# 15V_Regulated_Dual_Power_Supply_Circuit.net
KiCad netlist of a schematic drawn in EAGLE
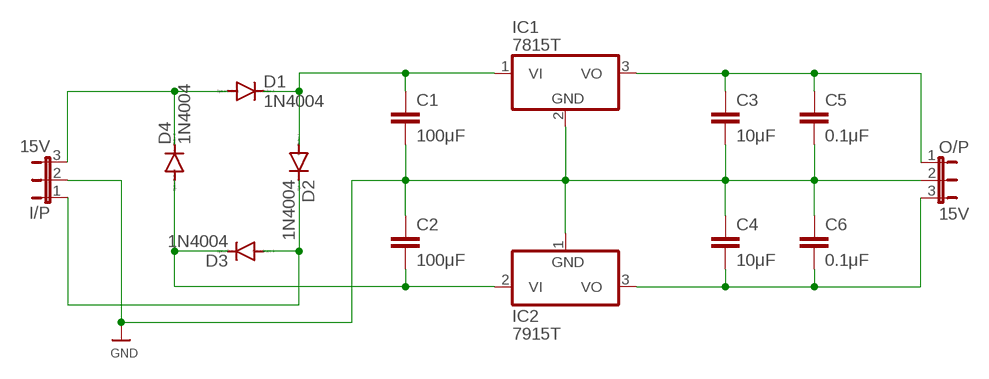
[diagram p0: schematic, sheet 1]

(export (version "E")
  (design (tool "Eeschema 10.0.6"))
  (components
    (comp (ref "C1")
      (value "100μF")
      (footprint "eagle-import:C2.5-2")
      (libsource (lib "eagle-import") (part "C2.5/2"))
    )
    (comp (ref "C2")
      (value "100μF")
      (footprint "eagle-import:C2.5-2")
      (libsource (lib "eagle-import") (part "C2.5/2"))
    )
    (comp (ref "C3")
      (value "10μF")
      (footprint "eagle-import:C2.5-2")
      (libsource (lib "eagle-import") (part "C2.5/2"))
    )
    (comp (ref "C4")
      (value "10μF")
      (footprint "eagle-import:C2.5-2")
      (libsource (lib "eagle-import") (part "C2.5/2"))
    )
    (comp (ref "C5")
      (value "0.1μF")
      (footprint "eagle-import:C2.5-2")
      (libsource (lib "eagle-import") (part "C2.5/2"))
    )
    (comp (ref "C6")
      (value "0.1μF")
      (footprint "eagle-import:C2.5-2")
      (libsource (lib "eagle-import") (part "C2.5/2"))
    )
    (comp (ref "D1")
      (value "1N4004")
      (footprint "eagle-import:DO41-10")
      (libsource (lib "eagle-import") (part "1N4004"))
    )
    (comp (ref "D2")
      (value "1N4004")
      (footprint "eagle-import:DO41-10")
      (libsource (lib "eagle-import") (part "1N4004"))
    )
    (comp (ref "D3")
      (value "1N4004")
      (footprint "eagle-import:DO41-10")
      (libsource (lib "eagle-import") (part "1N4004"))
    )
    (comp (ref "D4")
      (value "1N4004")
      (footprint "eagle-import:DO41-10")
      (libsource (lib "eagle-import") (part "1N4004"))
    )
    (comp (ref "I/P")
      (value "15V")
      (footprint "eagle-import:JP2")
      (libsource (lib "eagle-import") (part "JP2E"))
    )
    (comp (ref "IC1")
      (value "7815T")
      (footprint "eagle-import:TO220H")
      (libsource (lib "eagle-import") (part "78T15"))
    )
    (comp (ref "IC2")
      (value "7915T")
      (footprint "eagle-import:TO220H")
      (libsource (lib "eagle-import") (part "79T15"))
    )
    (comp (ref "O/P")
      (value "15V")
      (footprint "eagle-import:JP2")
      (libsource (lib "eagle-import") (part "JP2E"))
    )
  )
  (nets
    (net (code "1") (name "GND") (class "Default")
      (node (ref "C1") (pin "2") (pinfunction "2_2") (pintype "passive"))
      (node (ref "C2") (pin "1") (pinfunction "1_1") (pintype "passive"))
      (node (ref "C3") (pin "2") (pinfunction "2_2") (pintype "passive"))
      (node (ref "C4") (pin "1") (pinfunction "1_1") (pintype "passive"))
      (node (ref "C5") (pin "2") (pinfunction "2_2") (pintype "passive"))
      (node (ref "C6") (pin "1") (pinfunction "1_1") (pintype "passive"))
      (node (ref "I/P") (pin "2") (pinfunction "2_2") (pintype "passive"))
      (node (ref "IC1") (pin "2") (pinfunction "GND_2") (pintype "passive"))
      (node (ref "IC2") (pin "1") (pinfunction "GND_1") (pintype "passive"))
      (node (ref "O/P") (pin "2") (pinfunction "2_2") (pintype "passive"))
    )
    (net (code "2") (name "Net-(D1-PadA)") (class "Default")
      (node (ref "D1") (pin "A") (pinfunction "A_A") (pintype "passive"))
      (node (ref "D4") (pin "C") (pinfunction "C_C") (pintype "passive"))
      (node (ref "I/P") (pin "3") (pinfunction "3_3") (pintype "passive"))
    )
    (net (code "3") (name "Net-(D2-PadC)") (class "Default")
      (node (ref "D2") (pin "C") (pinfunction "C_C") (pintype "passive"))
      (node (ref "D3") (pin "A") (pinfunction "A_A") (pintype "passive"))
      (node (ref "I/P") (pin "1") (pinfunction "1_1") (pintype "passive"))
    )
    (net (code "4") (name "Net-(IC1-VI)") (class "Default")
      (node (ref "C1") (pin "1") (pinfunction "1_1") (pintype "passive"))
      (node (ref "D1") (pin "C") (pinfunction "C_C") (pintype "passive"))
      (node (ref "D2") (pin "A") (pinfunction "A_A") (pintype "passive"))
      (node (ref "IC1") (pin "1") (pinfunction "VI_1") (pintype "input"))
    )
    (net (code "5") (name "Net-(IC1-VO)") (class "Default")
      (node (ref "C3") (pin "1") (pinfunction "1_1") (pintype "passive"))
      (node (ref "C5") (pin "1") (pinfunction "1_1") (pintype "passive"))
      (node (ref "IC1") (pin "3") (pinfunction "VO_3") (pintype "passive"))
      (node (ref "O/P") (pin "1") (pinfunction "1_1") (pintype "passive"))
    )
    (net (code "6") (name "Net-(IC2-VI)") (class "Default")
      (node (ref "C2") (pin "2") (pinfunction "2_2") (pintype "passive"))
      (node (ref "D3") (pin "C") (pinfunction "C_C") (pintype "passive"))
      (node (ref "D4") (pin "A") (pinfunction "A_A") (pintype "passive"))
      (node (ref "IC2") (pin "2") (pinfunction "VI_2") (pintype "input"))
    )
    (net (code "7") (name "Net-(IC2-VO)") (class "Default")
      (node (ref "C4") (pin "2") (pinfunction "2_2") (pintype "passive"))
      (node (ref "C6") (pin "2") (pinfunction "2_2") (pintype "passive"))
      (node (ref "IC2") (pin "3") (pinfunction "VO_3") (pintype "passive"))
      (node (ref "O/P") (pin "3") (pinfunction "3_3") (pintype "passive"))
    )
  )
)
